# R2P_PS_v1.net
KiCad netlist of a schematic drawn in EAGLE
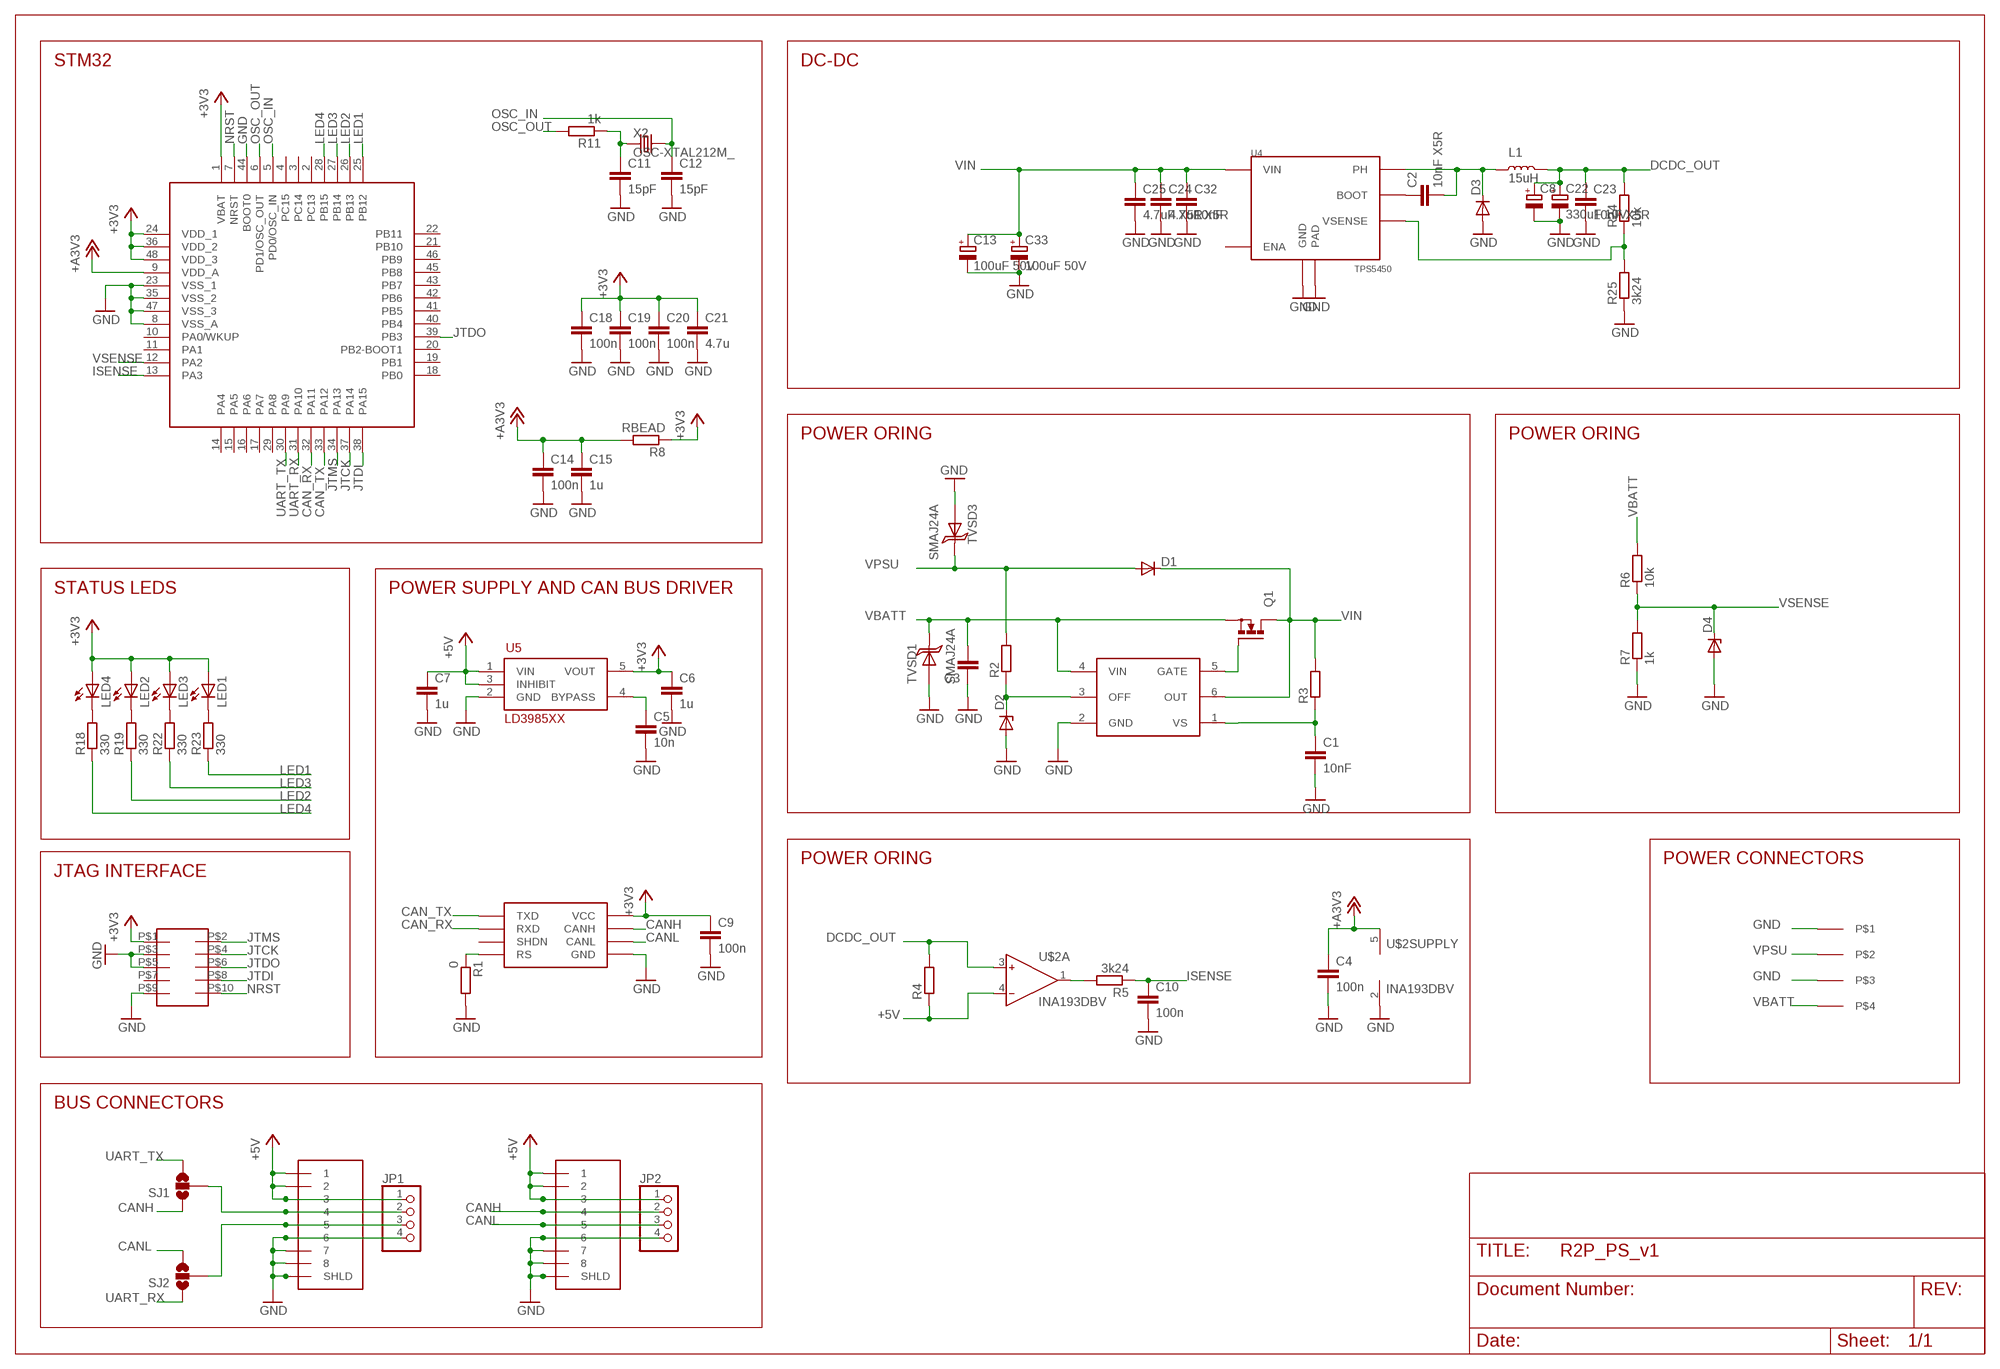
[diagram p0: schematic, sheet 1]

(export (version "E")
  (design (tool "Eeschema 10.0.6"))
  (components
    (comp (ref "1")
      (value "RJ45-43860")
      (footprint "eagle-import:0438600010")
      (libsource (lib "eagle-import") (part "RJ45-43860"))
    )
    (comp (ref "2")
      (value "RJ45-43860")
      (footprint "eagle-import:0438600010")
      (libsource (lib "eagle-import") (part "RJ45-43860"))
    )
    (comp (ref "C1")
      (value "10nF")
      (footprint "eagle-import:C0603")
      (libsource (lib "eagle-import") (part "C-EUC0603"))
    )
    (comp (ref "C2")
      (value "10nF X5R")
      (footprint "eagle-import:C0603")
      (libsource (lib "eagle-import") (part "C-EUC0603"))
    )
    (comp (ref "C3")
      (value "C-EUC0805")
      (footprint "eagle-import:C0805")
      (libsource (lib "eagle-import") (part "C-EUC0805"))
    )
    (comp (ref "C4")
      (value "100n")
      (footprint "eagle-import:C0603")
      (libsource (lib "eagle-import") (part "C-EUC0603"))
    )
    (comp (ref "C5")
      (value "10n")
      (footprint "eagle-import:C0603")
      (libsource (lib "eagle-import") (part "C-EUC0603"))
    )
    (comp (ref "C6")
      (value "1u")
      (footprint "eagle-import:C0603")
      (libsource (lib "eagle-import") (part "C-EUC0603"))
    )
    (comp (ref "C7")
      (value "1u")
      (footprint "eagle-import:C0603")
      (libsource (lib "eagle-import") (part "C-EUC0603"))
    )
    (comp (ref "C8")
      (value "CPOL-EUE5-10.5")
      (footprint "eagle-import:E5-10,5")
      (libsource (lib "eagle-import") (part "CPOL-EUE5-10.5"))
    )
    (comp (ref "C9")
      (value "100n")
      (footprint "eagle-import:C0603")
      (libsource (lib "eagle-import") (part "C-EUC0603"))
    )
    (comp (ref "C10")
      (value "100n")
      (footprint "eagle-import:C0603")
      (libsource (lib "eagle-import") (part "C-EUC0603"))
    )
    (comp (ref "C11")
      (value "15pF")
      (footprint "eagle-import:C0603")
      (libsource (lib "eagle-import") (part "C-EUC0603"))
    )
    (comp (ref "C12")
      (value "15pF")
      (footprint "eagle-import:C0603")
      (libsource (lib "eagle-import") (part "C-EUC0603"))
    )
    (comp (ref "C13")
      (value "100uF 50V")
      (footprint "eagle-import:E5-10,5")
      (libsource (lib "eagle-import") (part "CPOL-EUE5-10.5"))
    )
    (comp (ref "C14")
      (value "100n")
      (footprint "eagle-import:C0603")
      (libsource (lib "eagle-import") (part "C-EUC0603"))
    )
    (comp (ref "C15")
      (value "1u")
      (footprint "eagle-import:C0603")
      (libsource (lib "eagle-import") (part "C-EUC0603"))
    )
    (comp (ref "C18")
      (value "100n")
      (footprint "eagle-import:C0603")
      (libsource (lib "eagle-import") (part "C-EUC0603"))
    )
    (comp (ref "C19")
      (value "100n")
      (footprint "eagle-import:C0603")
      (libsource (lib "eagle-import") (part "C-EUC0603"))
    )
    (comp (ref "C20")
      (value "100n")
      (footprint "eagle-import:C0603")
      (libsource (lib "eagle-import") (part "C-EUC0603"))
    )
    (comp (ref "C21")
      (value "4.7u")
      (footprint "eagle-import:C0805")
      (libsource (lib "eagle-import") (part "C-EUC0805"))
    )
    (comp (ref "C22")
      (value "330uF 10V")
      (footprint "eagle-import:E2,5-7")
      (libsource (lib "eagle-import") (part "CPOL-EUE2.5-7"))
    )
    (comp (ref "C23")
      (value "10nF X5R")
      (footprint "eagle-import:C0603")
      (libsource (lib "eagle-import") (part "C-EUC0603"))
    )
    (comp (ref "C24")
      (value "4.7uF X5R")
      (footprint "eagle-import:C1210")
      (libsource (lib "eagle-import") (part "C-EUC1210"))
    )
    (comp (ref "C25")
      (value "4.7uF X5R")
      (footprint "eagle-import:C1210")
      (libsource (lib "eagle-import") (part "C-EUC1210"))
    )
    (comp (ref "C32")
      (value "10nF")
      (footprint "eagle-import:C0603")
      (libsource (lib "eagle-import") (part "C-EUC0603"))
    )
    (comp (ref "C33")
      (value "100uF 50V")
      (footprint "eagle-import:E2,5-7")
      (libsource (lib "eagle-import") (part "CPOL-EUE2.5-7"))
    )
    (comp (ref "D1")
      (value "DIODE-DO-214AC")
      (footprint "eagle-import:DO-214AC")
      (libsource (lib "eagle-import") (part "DIODE-DO-214AC"))
    )
    (comp (ref "D2")
      (value "ZENERSOD-323F")
      (footprint "eagle-import:SOD-323F")
      (libsource (lib "eagle-import") (part "ZENERSOD-323F"))
    )
    (comp (ref "D3")
      (value "DIODE-DO-214AC")
      (footprint "eagle-import:DO-214AC")
      (libsource (lib "eagle-import") (part "DIODE-DO-214AC"))
    )
    (comp (ref "D4")
      (value "ZENERSOD-323F")
      (footprint "eagle-import:SOD-323F")
      (libsource (lib "eagle-import") (part "ZENERSOD-323F"))
    )
    (comp (ref "JP1")
      (value "PINHD-1X4/90")
      (footprint "eagle-import:1X04_90")
      (libsource (lib "eagle-import") (part "PINHD-1X4/90"))
    )
    (comp (ref "JP2")
      (value "PINHD-1X4/90")
      (footprint "eagle-import:1X04_90")
      (libsource (lib "eagle-import") (part "PINHD-1X4/90"))
    )
    (comp (ref "L1")
      (value "15uH")
      (footprint "eagle-import:CDRH127")
      (libsource (lib "eagle-import") (part "CDRH127"))
    )
    (comp (ref "LED1")
      (value "LEDCHIPLED_0805")
      (footprint "eagle-import:CHIPLED_0805")
      (libsource (lib "eagle-import") (part "LEDCHIPLED_0805"))
    )
    (comp (ref "LED2")
      (value "LEDCHIPLED_0805")
      (footprint "eagle-import:CHIPLED_0805")
      (libsource (lib "eagle-import") (part "LEDCHIPLED_0805"))
    )
    (comp (ref "LED3")
      (value "LEDCHIPLED_0805")
      (footprint "eagle-import:CHIPLED_0805")
      (libsource (lib "eagle-import") (part "LEDCHIPLED_0805"))
    )
    (comp (ref "LED4")
      (value "LEDCHIPLED_0805")
      (footprint "eagle-import:CHIPLED_0805")
      (libsource (lib "eagle-import") (part "LEDCHIPLED_0805"))
    )
    (comp (ref "Q1")
      (value "N-MOSFET-SO8S")
      (footprint "eagle-import:SO-08")
      (libsource (lib "eagle-import") (part "N-MOSFET-SO8S"))
    )
    (comp (ref "R1")
      (value "0")
      (footprint "eagle-import:R0603")
      (libsource (lib "eagle-import") (part "R-EU_R0603"))
    )
    (comp (ref "R2")
      (value "R-EU_R0603")
      (footprint "eagle-import:R0603")
      (libsource (lib "eagle-import") (part "R-EU_R0603"))
    )
    (comp (ref "R3")
      (value "R-EU_R0603")
      (footprint "eagle-import:R0603")
      (libsource (lib "eagle-import") (part "R-EU_R0603"))
    )
    (comp (ref "R4")
      (value "R-EU_R2512")
      (footprint "eagle-import:R2512")
      (libsource (lib "eagle-import") (part "R-EU_R2512"))
    )
    (comp (ref "R5")
      (value "3k24")
      (footprint "eagle-import:R0603")
      (libsource (lib "eagle-import") (part "R-EU_R0603"))
    )
    (comp (ref "R6")
      (value "10k")
      (footprint "eagle-import:R0603")
      (libsource (lib "eagle-import") (part "R-EU_R0603"))
    )
    (comp (ref "R7")
      (value "1k")
      (footprint "eagle-import:R0603")
      (libsource (lib "eagle-import") (part "R-EU_R0603"))
    )
    (comp (ref "R8")
      (value "RBEAD")
      (footprint "eagle-import:R0603")
      (libsource (lib "eagle-import") (part "R-EU_R0603"))
    )
    (comp (ref "R11")
      (value "1k")
      (footprint "eagle-import:R0603")
      (libsource (lib "eagle-import") (part "R-EU_R0603"))
    )
    (comp (ref "R18")
      (value "330")
      (footprint "eagle-import:R0603")
      (libsource (lib "eagle-import") (part "R-EU_R0603"))
    )
    (comp (ref "R19")
      (value "330")
      (footprint "eagle-import:R0603")
      (libsource (lib "eagle-import") (part "R-EU_R0603"))
    )
    (comp (ref "R22")
      (value "330")
      (footprint "eagle-import:R0603")
      (libsource (lib "eagle-import") (part "R-EU_R0603"))
    )
    (comp (ref "R23")
      (value "330")
      (footprint "eagle-import:R0603")
      (libsource (lib "eagle-import") (part "R-EU_R0603"))
    )
    (comp (ref "R24")
      (value "10k")
      (footprint "eagle-import:R0603")
      (libsource (lib "eagle-import") (part "R-EU_R0603"))
    )
    (comp (ref "R25")
      (value "3k24")
      (footprint "eagle-import:R0603")
      (libsource (lib "eagle-import") (part "R-EU_R0603"))
    )
    (comp (ref "SJ1")
      (value "SOLDERJUMPER_2WAYPASTE1&2")
      (footprint "eagle-import:SJ_3_PASTE1&2")
      (libsource (lib "eagle-import") (part "SOLDERJUMPER_2WAYPASTE1&2"))
    )
    (comp (ref "SJ2")
      (value "SOLDERJUMPER_2WAYPASTE1&2")
      (footprint "eagle-import:SJ_3_PASTE1&2")
      (libsource (lib "eagle-import") (part "SOLDERJUMPER_2WAYPASTE1&2"))
    )
    (comp (ref "SOT1")
      (value "MAX3051")
      (footprint "eagle-import:SOT23-8L")
      (libsource (lib "eagle-import") (part "MAX3051"))
    )
    (comp (ref "TVSD1")
      (value "SMAJ24A")
      (footprint "eagle-import:SMA")
      (libsource (lib "eagle-import") (part "TVSDSMA"))
    )
    (comp (ref "TVSD3")
      (value "SMAJ24A")
      (footprint "eagle-import:SMA")
      (libsource (lib "eagle-import") (part "TVSDSMA"))
    )
    (comp (ref "U$1")
      (value "LM5050-1")
      (footprint "eagle-import:SOT23-6L")
      (libsource (lib "eagle-import") (part "LM5050-1"))
    )
    (comp (ref "U$2")
      (value "INA193DBV")
      (footprint "eagle-import:SOT23-5L")
      (libsource (lib "eagle-import") (part "INA193DBV"))
    )
    (comp (ref "U$3")
      (value "POWERCONN-4")
      (footprint "eagle-import:POWERCONN-4")
      (libsource (lib "eagle-import") (part "POWERCONN-4"))
    )
    (comp (ref "U$4")
      (value "FTSH-105")
      (footprint "eagle-import:FTSH-105")
      (libsource (lib "eagle-import") (part "FTSH-105"))
    )
    (comp (ref "U1")
      (value "STM32F103CX")
      (footprint "eagle-import:LQFP48")
      (libsource (lib "eagle-import") (part "STM32F103CX"))
    )
    (comp (ref "U4")
      (value "TPS5450")
      (footprint "eagle-import:POWERPAD-SO8")
      (libsource (lib "eagle-import") (part "TPS5450"))
    )
    (comp (ref "U5")
      (value "LD3985XX")
      (footprint "eagle-import:SOT23-5L")
      (libsource (lib "eagle-import") (part "LD3985XX"))
    )
    (comp (ref "X2")
      (value "OSC-XTAL212M_")
      (footprint "eagle-import:4X6")
      (libsource (lib "eagle-import") (part "OSC-XTAL212M_"))
    )
  )
  (nets
    (net (code "1") (name "+3V3") (class "Default")
      (node (ref "C18") (pin "1") (pinfunction "1_1") (pintype "passive"))
      (node (ref "C19") (pin "1") (pinfunction "1_1") (pintype "passive"))
      (node (ref "C20") (pin "1") (pinfunction "1_1") (pintype "passive"))
      (node (ref "C21") (pin "1") (pinfunction "1_1") (pintype "passive"))
      (node (ref "C6") (pin "1") (pinfunction "1_1") (pintype "passive"))
      (node (ref "C9") (pin "1") (pinfunction "1_1") (pintype "passive"))
      (node (ref "LED1") (pin "A") (pinfunction "A_A") (pintype "passive"))
      (node (ref "LED2") (pin "A") (pinfunction "A_A") (pintype "passive"))
      (node (ref "LED3") (pin "A") (pinfunction "A_A") (pintype "passive"))
      (node (ref "LED4") (pin "A") (pinfunction "A_A") (pintype "passive"))
      (node (ref "R8") (pin "1") (pinfunction "1_1") (pintype "passive"))
      (node (ref "SOT1") (pin "P$3") (pinfunction "VCC_P$3") (pintype "bidirectional"))
      (node (ref "U$4") (pin "P$1") (pinfunction "P$1_P$1") (pintype "bidirectional"))
      (node (ref "U1") (pin "1") (pinfunction "VBAT_1") (pintype "bidirectional"))
      (node (ref "U1") (pin "24") (pinfunction "VDD_1_24") (pintype "bidirectional"))
      (node (ref "U1") (pin "36") (pinfunction "VDD_2_36") (pintype "bidirectional"))
      (node (ref "U1") (pin "48") (pinfunction "VDD_3_48") (pintype "bidirectional"))
      (node (ref "U5") (pin "5") (pinfunction "VOUT_5") (pintype "bidirectional"))
    )
    (net (code "2") (name "+5V") (class "Default")
      (node (ref "1") (pin "P$1") (pinfunction "1_P$1") (pintype "bidirectional"))
      (node (ref "1") (pin "P$2") (pinfunction "2_P$2") (pintype "bidirectional"))
      (node (ref "1") (pin "P$3") (pinfunction "3_P$3") (pintype "bidirectional"))
      (node (ref "2") (pin "P$1") (pinfunction "1_P$1") (pintype "bidirectional"))
      (node (ref "2") (pin "P$2") (pinfunction "2_P$2") (pintype "bidirectional"))
      (node (ref "2") (pin "P$3") (pinfunction "3_P$3") (pintype "bidirectional"))
      (node (ref "C7") (pin "1") (pinfunction "1_1") (pintype "passive"))
      (node (ref "JP1") (pin "1") (pinfunction "1_1") (pintype "passive"))
      (node (ref "JP2") (pin "1") (pinfunction "1_1") (pintype "passive"))
      (node (ref "R4") (pin "1") (pinfunction "1_1") (pintype "passive"))
      (node (ref "U$2") (pin "4") (pinfunction "IN-_4") (pintype "input"))
      (node (ref "U5") (pin "1") (pinfunction "VIN_1") (pintype "bidirectional"))
      (node (ref "U5") (pin "3") (pinfunction "INHIBIT_3") (pintype "bidirectional"))
    )
    (net (code "3") (name "+A3V3") (class "Default")
      (node (ref "C14") (pin "1") (pinfunction "1_1") (pintype "passive"))
      (node (ref "C15") (pin "1") (pinfunction "1_1") (pintype "passive"))
      (node (ref "C4") (pin "1") (pinfunction "1_1") (pintype "passive"))
      (node (ref "R8") (pin "2") (pinfunction "2_2") (pintype "passive"))
      (node (ref "U$2") (pin "5") (pinfunction "V+_5") (pintype "power_in"))
      (node (ref "U1") (pin "9") (pinfunction "VDD_A_9") (pintype "bidirectional"))
    )
    (net (code "4") (name "/CANH") (class "Default")
      (node (ref "2") (pin "P$4") (pinfunction "4_P$4") (pintype "bidirectional"))
      (node (ref "JP2") (pin "2") (pinfunction "2_2") (pintype "passive"))
      (node (ref "SJ1") (pin "1") (pinfunction "1_1") (pintype "passive"))
      (node (ref "SOT1") (pin "P$7") (pinfunction "CANH_P$7") (pintype "bidirectional"))
    )
    (net (code "5") (name "/CANL") (class "Default")
      (node (ref "2") (pin "P$5") (pinfunction "5_P$5") (pintype "bidirectional"))
      (node (ref "JP2") (pin "3") (pinfunction "3_3") (pintype "passive"))
      (node (ref "SJ2") (pin "3") (pinfunction "3_3") (pintype "passive"))
      (node (ref "SOT1") (pin "P$6") (pinfunction "CANL_P$6") (pintype "bidirectional"))
    )
    (net (code "6") (name "/CAN_RX") (class "Default")
      (node (ref "SOT1") (pin "P$4") (pinfunction "RXD_P$4") (pintype "bidirectional"))
      (node (ref "U1") (pin "32") (pinfunction "PA11_32") (pintype "bidirectional"))
    )
    (net (code "7") (name "/CAN_TX") (class "Default")
      (node (ref "SOT1") (pin "P$1") (pinfunction "TXD_P$1") (pintype "bidirectional"))
      (node (ref "U1") (pin "33") (pinfunction "PA12_33") (pintype "bidirectional"))
    )
    (net (code "8") (name "/DCDC_OUT") (class "Default")
      (node (ref "C22") (pin "+") (pinfunction "+_+") (pintype "passive"))
      (node (ref "C23") (pin "1") (pinfunction "1_1") (pintype "passive"))
      (node (ref "C8") (pin "+") (pinfunction "+_+") (pintype "passive"))
      (node (ref "L1") (pin "P$2") (pinfunction "2_P$2") (pintype "passive"))
      (node (ref "R24") (pin "2") (pinfunction "2_2") (pintype "passive"))
      (node (ref "R4") (pin "2") (pinfunction "2_2") (pintype "passive"))
      (node (ref "U$2") (pin "3") (pinfunction "IN+_3") (pintype "input"))
    )
    (net (code "9") (name "/ISENSE") (class "Default")
      (node (ref "C10") (pin "1") (pinfunction "1_1") (pintype "passive"))
      (node (ref "R5") (pin "1") (pinfunction "1_1") (pintype "passive"))
      (node (ref "U1") (pin "13") (pinfunction "PA3_13") (pintype "bidirectional"))
    )
    (net (code "10") (name "/JTCK") (class "Default")
      (node (ref "U$4") (pin "P$4") (pinfunction "P$4_P$4") (pintype "bidirectional"))
      (node (ref "U1") (pin "37") (pinfunction "PA14_37") (pintype "bidirectional"))
    )
    (net (code "11") (name "/JTDI") (class "Default")
      (node (ref "U$4") (pin "P$8") (pinfunction "P$8_P$8") (pintype "bidirectional"))
      (node (ref "U1") (pin "38") (pinfunction "PA15_38") (pintype "bidirectional"))
    )
    (net (code "12") (name "/JTDO") (class "Default")
      (node (ref "U$4") (pin "P$6") (pinfunction "P$6_P$6") (pintype "bidirectional"))
      (node (ref "U1") (pin "39") (pinfunction "PB3_39") (pintype "bidirectional"))
    )
    (net (code "13") (name "/JTMS") (class "Default")
      (node (ref "U$4") (pin "P$2") (pinfunction "P$2_P$2") (pintype "bidirectional"))
      (node (ref "U1") (pin "34") (pinfunction "PA13_34") (pintype "bidirectional"))
    )
    (net (code "14") (name "/LED1") (class "Default")
      (node (ref "R23") (pin "1") (pinfunction "1_1") (pintype "passive"))
      (node (ref "U1") (pin "25") (pinfunction "PB12_25") (pintype "bidirectional"))
    )
    (net (code "15") (name "/LED2") (class "Default")
      (node (ref "R19") (pin "1") (pinfunction "1_1") (pintype "passive"))
      (node (ref "U1") (pin "26") (pinfunction "PB13_26") (pintype "bidirectional"))
    )
    (net (code "16") (name "/LED3") (class "Default")
      (node (ref "R22") (pin "1") (pinfunction "1_1") (pintype "passive"))
      (node (ref "U1") (pin "27") (pinfunction "PB14_27") (pintype "bidirectional"))
    )
    (net (code "17") (name "/LED4") (class "Default")
      (node (ref "R18") (pin "1") (pinfunction "1_1") (pintype "passive"))
      (node (ref "U1") (pin "28") (pinfunction "PB15_28") (pintype "bidirectional"))
    )
    (net (code "18") (name "/NRST") (class "Default")
      (node (ref "U$4") (pin "P$10") (pinfunction "P$10_P$10") (pintype "bidirectional"))
      (node (ref "U1") (pin "7") (pinfunction "NRST_7") (pintype "bidirectional"))
    )
    (net (code "19") (name "/OSC_IN") (class "Default")
      (node (ref "C12") (pin "1") (pinfunction "1_1") (pintype "passive"))
      (node (ref "U1") (pin "5") (pinfunction "PD0/OSC_IN_5") (pintype "bidirectional"))
      (node (ref "X2") (pin "2") (pinfunction "X2_2") (pintype "bidirectional"))
    )
    (net (code "20") (name "/OSC_OUT") (class "Default")
      (node (ref "R11") (pin "2") (pinfunction "2_2") (pintype "passive"))
      (node (ref "U1") (pin "6") (pinfunction "PD1/OSC_OUT_6") (pintype "bidirectional"))
    )
    (net (code "21") (name "/UART_RX") (class "Default")
      (node (ref "SJ2") (pin "1") (pinfunction "1_1") (pintype "passive"))
      (node (ref "U1") (pin "31") (pinfunction "PA10_31") (pintype "bidirectional"))
    )
    (net (code "22") (name "/UART_TX") (class "Default")
      (node (ref "SJ1") (pin "3") (pinfunction "3_3") (pintype "passive"))
      (node (ref "U1") (pin "30") (pinfunction "PA9_30") (pintype "bidirectional"))
    )
    (net (code "23") (name "/VBATT") (class "Default")
      (node (ref "C3") (pin "2") (pinfunction "2_2") (pintype "passive"))
      (node (ref "Q1") (pin "1") (pinfunction "S_1") (pintype "passive"))
      (node (ref "Q1") (pin "2") (pinfunction "S_2") (pintype "passive"))
      (node (ref "Q1") (pin "3") (pinfunction "S_3") (pintype "passive"))
      (node (ref "R6") (pin "2") (pinfunction "2_2") (pintype "passive"))
      (node (ref "TVSD1") (pin "C") (pinfunction "K_C") (pintype "bidirectional"))
      (node (ref "U$1") (pin "4") (pinfunction "VIN_4") (pintype "bidirectional"))
      (node (ref "U$3") (pin "P$4") (pinfunction "P$4_P$4") (pintype "bidirectional"))
    )
    (net (code "24") (name "/VIN") (class "Default")
      (node (ref "C13") (pin "+") (pinfunction "+_+") (pintype "passive"))
      (node (ref "C24") (pin "1") (pinfunction "1_1") (pintype "passive"))
      (node (ref "C25") (pin "1") (pinfunction "1_1") (pintype "passive"))
      (node (ref "C32") (pin "1") (pinfunction "1_1") (pintype "passive"))
      (node (ref "C33") (pin "+") (pinfunction "+_+") (pintype "passive"))
      (node (ref "D1") (pin "C") (pinfunction "C_C") (pintype "passive"))
      (node (ref "Q1") (pin "5") (pinfunction "D_5") (pintype "passive"))
      (node (ref "Q1") (pin "6") (pinfunction "D_6") (pintype "passive"))
      (node (ref "Q1") (pin "7") (pinfunction "D_7") (pintype "passive"))
      (node (ref "Q1") (pin "8") (pinfunction "D_8") (pintype "passive"))
      (node (ref "R3") (pin "2") (pinfunction "2_2") (pintype "passive"))
      (node (ref "U$1") (pin "6") (pinfunction "OUT_6") (pintype "bidirectional"))
      (node (ref "U4") (pin "P7") (pinfunction "VIN_P7") (pintype "bidirectional"))
    )
    (net (code "25") (name "/VPSU") (class "Default")
      (node (ref "D1") (pin "A") (pinfunction "A_A") (pintype "passive"))
      (node (ref "R2") (pin "2") (pinfunction "2_2") (pintype "passive"))
      (node (ref "TVSD3") (pin "C") (pinfunction "K_C") (pintype "bidirectional"))
      (node (ref "U$3") (pin "P$2") (pinfunction "P$2_P$2") (pintype "bidirectional"))
    )
    (net (code "26") (name "/VSENSE") (class "Default")
      (node (ref "D4") (pin "C") (pinfunction "C_C") (pintype "passive"))
      (node (ref "R6") (pin "1") (pinfunction "1_1") (pintype "passive"))
      (node (ref "R7") (pin "2") (pinfunction "2_2") (pintype "passive"))
      (node (ref "U1") (pin "12") (pinfunction "PA2_12") (pintype "bidirectional"))
    )
    (net (code "27") (name "GND") (class "Default")
      (node (ref "1") (pin "P$10") (pinfunction "P$1_P$10") (pintype "power_in"))
      (node (ref "1") (pin "P$6") (pinfunction "6_P$6") (pintype "bidirectional"))
      (node (ref "1") (pin "P$7") (pinfunction "7_P$7") (pintype "bidirectional"))
      (node (ref "1") (pin "P$8") (pinfunction "8_P$8") (pintype "bidirectional"))
      (node (ref "1") (pin "P$9") (pinfunction "SHLD_P$9") (pintype "power_in"))
      (node (ref "2") (pin "P$10") (pinfunction "P$1_P$10") (pintype "power_in"))
      (node (ref "2") (pin "P$6") (pinfunction "6_P$6") (pintype "bidirectional"))
      (node (ref "2") (pin "P$7") (pinfunction "7_P$7") (pintype "bidirectional"))
      (node (ref "2") (pin "P$8") (pinfunction "8_P$8") (pintype "bidirectional"))
      (node (ref "2") (pin "P$9") (pinfunction "SHLD_P$9") (pintype "power_in"))
      (node (ref "C1") (pin "2") (pinfunction "2_2") (pintype "passive"))
      (node (ref "C10") (pin "2") (pinfunction "2_2") (pintype "passive"))
      (node (ref "C11") (pin "2") (pinfunction "2_2") (pintype "passive"))
      (node (ref "C12") (pin "2") (pinfunction "2_2") (pintype "passive"))
      (node (ref "C13") (pin "-") (pinfunction "-_-") (pintype "passive"))
      (node (ref "C14") (pin "2") (pinfunction "2_2") (pintype "passive"))
      (node (ref "C15") (pin "2") (pinfunction "2_2") (pintype "passive"))
      (node (ref "C18") (pin "2") (pinfunction "2_2") (pintype "passive"))
      (node (ref "C19") (pin "2") (pinfunction "2_2") (pintype "passive"))
      (node (ref "C20") (pin "2") (pinfunction "2_2") (pintype "passive"))
      (node (ref "C21") (pin "2") (pinfunction "2_2") (pintype "passive"))
      (node (ref "C22") (pin "-") (pinfunction "-_-") (pintype "passive"))
      (node (ref "C23") (pin "2") (pinfunction "2_2") (pintype "passive"))
      (node (ref "C24") (pin "2") (pinfunction "2_2") (pintype "passive"))
      (node (ref "C25") (pin "2") (pinfunction "2_2") (pintype "passive"))
      (node (ref "C3") (pin "1") (pinfunction "1_1") (pintype "passive"))
      (node (ref "C32") (pin "2") (pinfunction "2_2") (pintype "passive"))
      (node (ref "C33") (pin "-") (pinfunction "-_-") (pintype "passive"))
      (node (ref "C4") (pin "2") (pinfunction "2_2") (pintype "passive"))
      (node (ref "C5") (pin "2") (pinfunction "2_2") (pintype "passive"))
      (node (ref "C6") (pin "2") (pinfunction "2_2") (pintype "passive"))
      (node (ref "C7") (pin "2") (pinfunction "2_2") (pintype "passive"))
      (node (ref "C8") (pin "-") (pinfunction "-_-") (pintype "passive"))
      (node (ref "C9") (pin "2") (pinfunction "2_2") (pintype "passive"))
      (node (ref "D2") (pin "A") (pinfunction "A_A") (pintype "passive"))
      (node (ref "D3") (pin "A") (pinfunction "A_A") (pintype "passive"))
      (node (ref "D4") (pin "A") (pinfunction "A_A") (pintype "passive"))
      (node (ref "JP1") (pin "4") (pinfunction "4_4") (pintype "passive"))
      (node (ref "JP2") (pin "4") (pinfunction "4_4") (pintype "passive"))
      (node (ref "R1") (pin "2") (pinfunction "2_2") (pintype "passive"))
      (node (ref "R25") (pin "1") (pinfunction "1_1") (pintype "passive"))
      (node (ref "R7") (pin "1") (pinfunction "1_1") (pintype "passive"))
      (node (ref "SOT1") (pin "P$2") (pinfunction "GND_P$2") (pintype "bidirectional"))
      (node (ref "TVSD1") (pin "A") (pinfunction "A_A") (pintype "bidirectional"))
      (node (ref "TVSD3") (pin "A") (pinfunction "A_A") (pintype "bidirectional"))
      (node (ref "U$1") (pin "2") (pinfunction "GND_2") (pintype "bidirectional"))
      (node (ref "U$2") (pin "2") (pinfunction "V-_2") (pintype "power_in"))
      (node (ref "U$3") (pin "P$1") (pinfunction "P$1_P$1") (pintype "bidirectional"))
      (node (ref "U$3") (pin "P$3") (pinfunction "P$3_P$3") (pintype "bidirectional"))
      (node (ref "U$4") (pin "P$3") (pinfunction "P$3_P$3") (pintype "bidirectional"))
      (node (ref "U$4") (pin "P$5") (pinfunction "P$5_P$5") (pintype "bidirectional"))
      (node (ref "U$4") (pin "P$9") (pinfunction "P$9_P$9") (pintype "bidirectional"))
      (node (ref "U1") (pin "23") (pinfunction "VSS_1_23") (pintype "bidirectional"))
      (node (ref "U1") (pin "35") (pinfunction "VSS_2_35") (pintype "bidirectional"))
      (node (ref "U1") (pin "44") (pinfunction "BOOT0_44") (pintype "bidirectional"))
      (node (ref "U1") (pin "47") (pinfunction "VSS_3_47") (pintype "bidirectional"))
      (node (ref "U1") (pin "8") (pinfunction "VSS_A_8") (pintype "bidirectional"))
      (node (ref "U4") (pin "P6") (pinfunction "GND_P6") (pintype "bidirectional"))
      (node (ref "U4") (pin "PAD") (pinfunction "PAD_PAD") (pintype "bidirectional"))
      (node (ref "U5") (pin "2") (pinfunction "GND_2") (pintype "bidirectional"))
    )
    (net (code "28") (name "Net-(1-4)") (class "Default")
      (node (ref "1") (pin "P$4") (pinfunction "4_P$4") (pintype "bidirectional"))
      (node (ref "JP1") (pin "2") (pinfunction "2_2") (pintype "passive"))
      (node (ref "SJ1") (pin "2") (pinfunction "2_2") (pintype "passive"))
    )
    (net (code "29") (name "Net-(1-5)") (class "Default")
      (node (ref "1") (pin "P$5") (pinfunction "5_P$5") (pintype "bidirectional"))
      (node (ref "JP1") (pin "3") (pinfunction "3_3") (pintype "passive"))
      (node (ref "SJ2") (pin "2") (pinfunction "2_2") (pintype "passive"))
    )
    (net (code "30") (name "Net-(L1-1)") (class "Default")
      (node (ref "C2") (pin "2") (pinfunction "2_2") (pintype "passive"))
      (node (ref "D3") (pin "C") (pinfunction "C_C") (pintype "passive"))
      (node (ref "L1") (pin "P$1") (pinfunction "1_P$1") (pintype "passive"))
      (node (ref "U4") (pin "P8") (pinfunction "PH_P8") (pintype "bidirectional"))
    )
    (net (code "31") (name "Net-(LED1-PadC)") (class "Default")
      (node (ref "LED1") (pin "C") (pinfunction "C_C") (pintype "passive"))
      (node (ref "R23") (pin "2") (pinfunction "2_2") (pintype "passive"))
    )
    (net (code "32") (name "Net-(LED2-PadC)") (class "Default")
      (node (ref "LED2") (pin "C") (pinfunction "C_C") (pintype "passive"))
      (node (ref "R19") (pin "2") (pinfunction "2_2") (pintype "passive"))
    )
    (net (code "33") (name "Net-(LED3-PadC)") (class "Default")
      (node (ref "LED3") (pin "C") (pinfunction "C_C") (pintype "passive"))
      (node (ref "R22") (pin "2") (pinfunction "2_2") (pintype "passive"))
    )
    (net (code "34") (name "Net-(LED4-PadC)") (class "Default")
      (node (ref "LED4") (pin "C") (pinfunction "C_C") (pintype "passive"))
      (node (ref "R18") (pin "2") (pinfunction "2_2") (pintype "passive"))
    )
    (net (code "35") (name "Net-(Q1-G)") (class "Default")
      (node (ref "Q1") (pin "4") (pinfunction "G_4") (pintype "passive"))
      (node (ref "U$1") (pin "5") (pinfunction "GATE_5") (pintype "bidirectional"))
    )
    (net (code "36") (name "Net-(SOT1-RS)") (class "Default")
      (node (ref "R1") (pin "1") (pinfunction "1_1") (pintype "passive"))
      (node (ref "SOT1") (pin "P$8") (pinfunction "RS_P$8") (pintype "bidirectional"))
    )
    (net (code "37") (name "Net-(U$1-OFF)") (class "Default")
      (node (ref "D2") (pin "C") (pinfunction "C_C") (pintype "passive"))
      (node (ref "R2") (pin "1") (pinfunction "1_1") (pintype "passive"))
      (node (ref "U$1") (pin "3") (pinfunction "OFF_3") (pintype "bidirectional"))
    )
    (net (code "38") (name "Net-(U$1-VS)") (class "Default")
      (node (ref "C1") (pin "1") (pinfunction "1_1") (pintype "passive"))
      (node (ref "R3") (pin "1") (pinfunction "1_1") (pintype "passive"))
      (node (ref "U$1") (pin "1") (pinfunction "VS_1") (pintype "bidirectional"))
    )
    (net (code "39") (name "Net-(U$2A-OUT)") (class "Default")
      (node (ref "R5") (pin "2") (pinfunction "2_2") (pintype "passive"))
      (node (ref "U$2") (pin "1") (pinfunction "OUT_1") (pintype "output"))
    )
    (net (code "40") (name "Net-(U4-BOOT)") (class "Default")
      (node (ref "C2") (pin "1") (pinfunction "1_1") (pintype "passive"))
      (node (ref "U4") (pin "P1") (pinfunction "BOOT_P1") (pintype "bidirectional"))
    )
    (net (code "41") (name "Net-(U4-VSENSE)") (class "Default")
      (node (ref "R24") (pin "1") (pinfunction "1_1") (pintype "passive"))
      (node (ref "R25") (pin "2") (pinfunction "2_2") (pintype "passive"))
      (node (ref "U4") (pin "P4") (pinfunction "VSENSE_P4") (pintype "bidirectional"))
    )
    (net (code "42") (name "Net-(U5-BYPASS)") (class "Default")
      (node (ref "C5") (pin "1") (pinfunction "1_1") (pintype "passive"))
      (node (ref "U5") (pin "4") (pinfunction "BYPASS_4") (pintype "bidirectional"))
    )
    (net (code "43") (name "Net-(X2-X1)") (class "Default")
      (node (ref "C11") (pin "1") (pinfunction "1_1") (pintype "passive"))
      (node (ref "R11") (pin "1") (pinfunction "1_1") (pintype "passive"))
      (node (ref "X2") (pin "1") (pinfunction "X1_1") (pintype "bidirectional"))
    )
    (net (code "44") (name "unconnected-(SOT1-SHDN-PadP$5)") (class "Default")
      (node (ref "SOT1") (pin "P$5") (pinfunction "SHDN_P$5") (pintype "bidirectional"))
    )
    (net (code "45") (name "unconnected-(U$4-PadP$7)") (class "Default")
      (node (ref "U$4") (pin "P$7") (pinfunction "P$7_P$7") (pintype "bidirectional"))
    )
    (net (code "46") (name "unconnected-(U1-PA0{slash}WKUP-Pad10)") (class "Default")
      (node (ref "U1") (pin "10") (pinfunction "PA0/WKUP_10") (pintype "bidirectional"))
    )
    (net (code "47") (name "unconnected-(U1-PA1-Pad11)") (class "Default")
      (node (ref "U1") (pin "11") (pinfunction "PA1_11") (pintype "bidirectional"))
    )
    (net (code "48") (name "unconnected-(U1-PA4-Pad14)") (class "Default")
      (node (ref "U1") (pin "14") (pinfunction "PA4_14") (pintype "bidirectional"))
    )
    (net (code "49") (name "unconnected-(U1-PA5-Pad15)") (class "Default")
      (node (ref "U1") (pin "15") (pinfunction "PA5_15") (pintype "bidirectional"))
    )
    (net (code "50") (name "unconnected-(U1-PA6-Pad16)") (class "Default")
      (node (ref "U1") (pin "16") (pinfunction "PA6_16") (pintype "bidirectional"))
    )
    (net (code "51") (name "unconnected-(U1-PA7-Pad17)") (class "Default")
      (node (ref "U1") (pin "17") (pinfunction "PA7_17") (pintype "bidirectional"))
    )
    (net (code "52") (name "unconnected-(U1-PA8-Pad29)") (class "Default")
      (node (ref "U1") (pin "29") (pinfunction "PA8_29") (pintype "bidirectional"))
    )
    (net (code "53") (name "unconnected-(U1-PB0-Pad18)") (class "Default")
      (node (ref "U1") (pin "18") (pinfunction "PB0_18") (pintype "bidirectional"))
    )
    (net (code "54") (name "unconnected-(U1-PB1-Pad19)") (class "Default")
      (node (ref "U1") (pin "19") (pinfunction "PB1_19") (pintype "bidirectional"))
    )
    (net (code "55") (name "unconnected-(U1-PB2-BOOT1-Pad20)") (class "Default")
      (node (ref "U1") (pin "20") (pinfunction "PB2-BOOT1_20") (pintype "bidirectional"))
    )
    (net (code "56") (name "unconnected-(U1-PB4-Pad40)") (class "Default")
      (node (ref "U1") (pin "40") (pinfunction "PB4_40") (pintype "bidirectional"))
    )
    (net (code "57") (name "unconnected-(U1-PB5-Pad41)") (class "Default")
      (node (ref "U1") (pin "41") (pinfunction "PB5_41") (pintype "bidirectional"))
    )
    (net (code "58") (name "unconnected-(U1-PB6-Pad42)") (class "Default")
      (node (ref "U1") (pin "42") (pinfunction "PB6_42") (pintype "bidirectional"))
    )
    (net (code "59") (name "unconnected-(U1-PB7-Pad43)") (class "Default")
      (node (ref "U1") (pin "43") (pinfunction "PB7_43") (pintype "bidirectional"))
    )
    (net (code "60") (name "unconnected-(U1-PB8-Pad45)") (class "Default")
      (node (ref "U1") (pin "45") (pinfunction "PB8_45") (pintype "bidirectional"))
    )
    (net (code "61") (name "unconnected-(U1-PB9-Pad46)") (class "Default")
      (node (ref "U1") (pin "46") (pinfunction "PB9_46") (pintype "bidirectional"))
    )
    (net (code "62") (name "unconnected-(U1-PB10-Pad21)") (class "Default")
      (node (ref "U1") (pin "21") (pinfunction "PB10_21") (pintype "bidirectional"))
    )
    (net (code "63") (name "unconnected-(U1-PB11-Pad22)") (class "Default")
      (node (ref "U1") (pin "22") (pinfunction "PB11_22") (pintype "bidirectional"))
    )
    (net (code "64") (name "unconnected-(U1-PC13-Pad2)") (class "Default")
      (node (ref "U1") (pin "2") (pinfunction "PC13_2") (pintype "bidirectional"))
    )
    (net (code "65") (name "unconnected-(U1-PC14-Pad3)") (class "Default")
      (node (ref "U1") (pin "3") (pinfunction "PC14_3") (pintype "bidirectional"))
    )
    (net (code "66") (name "unconnected-(U1-PC15-Pad4)") (class "Default")
      (node (ref "U1") (pin "4") (pinfunction "PC15_4") (pintype "bidirectional"))
    )
    (net (code "67") (name "unconnected-(U4-ENA-PadP5)") (class "Default")
      (node (ref "U4") (pin "P5") (pinfunction "ENA_P5") (pintype "bidirectional"))
    )
  )
)
